# Battery.net
KiCad netlist of a schematic drawn in Altium Designer
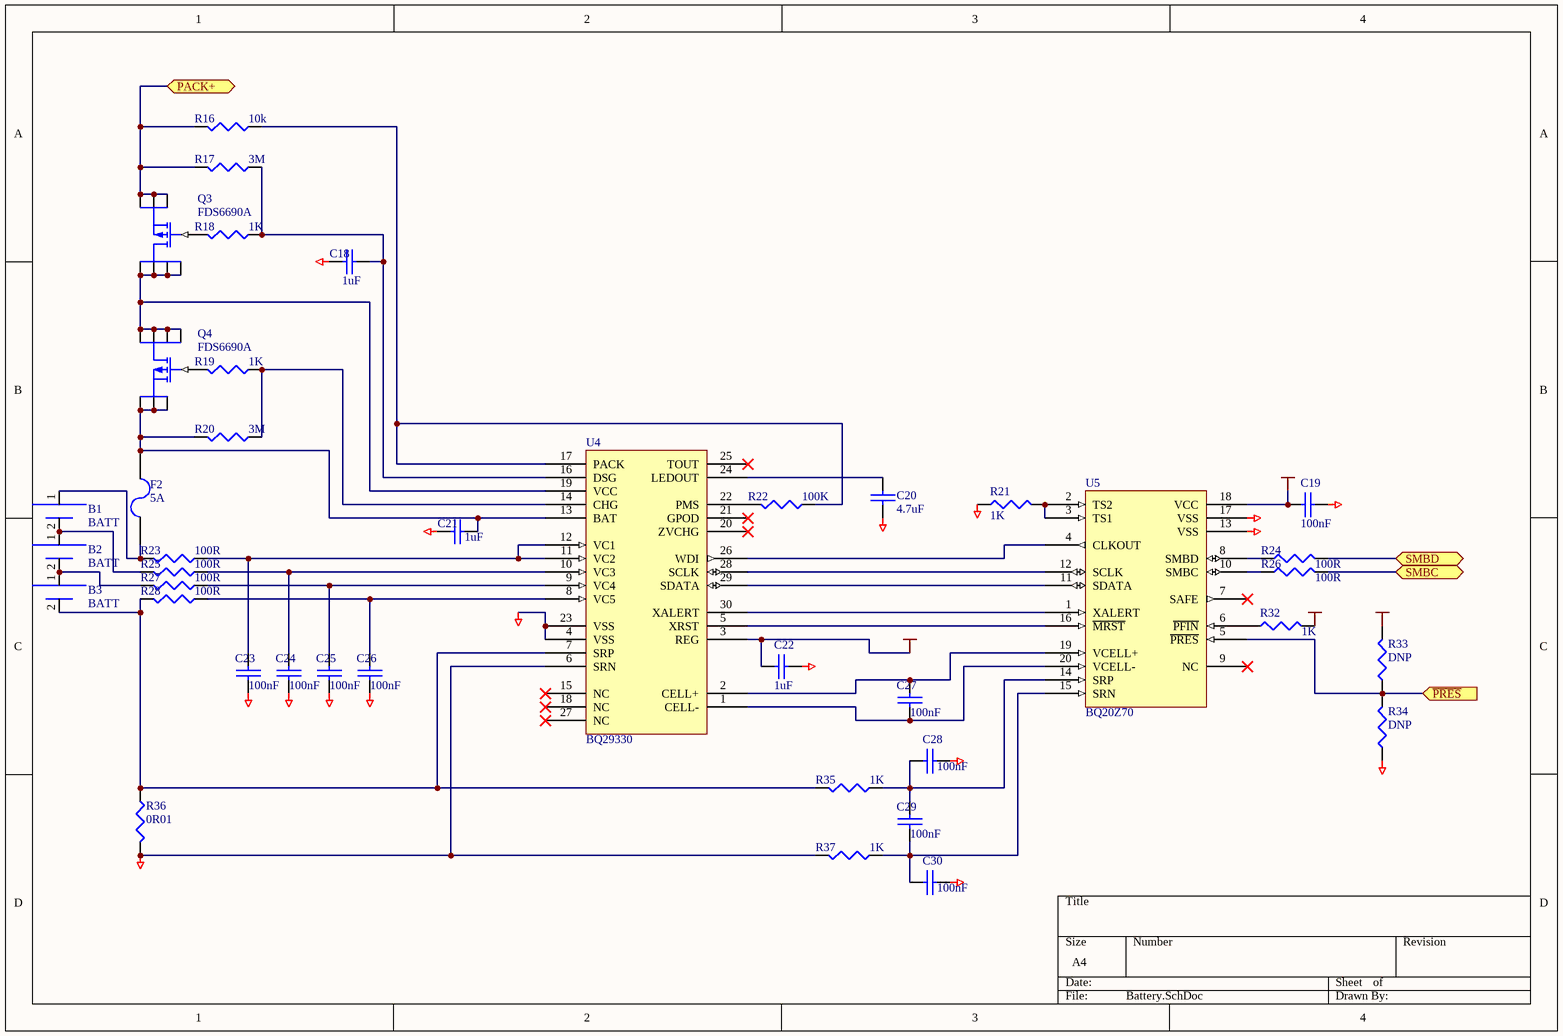
[diagram p0: Battery.SchDoc]

(export (version "E")
  (design (tool "Eeschema 10.0.6"))
  (components
    (comp (ref "B1")
      (value "BATT")
      (footprint "StandardLiIonCell")
      (libsource (lib "Miscellaneous") (part "BATT"))
    )
    (comp (ref "B2")
      (value "BATT")
      (footprint "StandardLiIonCell")
      (libsource (lib "Miscellaneous") (part "BATT"))
    )
    (comp (ref "B3")
      (value "BATT")
      (footprint "StandardLiIonCell")
      (libsource (lib "Miscellaneous") (part "BATT"))
    )
    (comp (ref "C18")
      (value "1uF")
      (footprint "0805")
      (description "Capacitor")
      (libsource (lib "*") (part "CAP"))
    )
    (comp (ref "C19")
      (value "100nF")
      (footprint "0603")
      (description "Capacitor")
      (libsource (lib "*") (part "CAP"))
    )
    (comp (ref "C20")
      (value "4.7uF")
      (footprint "0805")
      (description "Capacitor")
      (libsource (lib "*") (part "CAP"))
    )
    (comp (ref "C21")
      (value "1uF")
      (footprint "0805")
      (description "Capacitor")
      (libsource (lib "*") (part "CAP"))
    )
    (comp (ref "C22")
      (value "1uF")
      (footprint "0805")
      (description "Capacitor")
      (libsource (lib "*") (part "CAP"))
    )
    (comp (ref "C23")
      (value "100nF")
      (footprint "0603")
      (description "Capacitor")
      (libsource (lib "*") (part "CAP"))
    )
    (comp (ref "C24")
      (value "100nF")
      (footprint "0603")
      (description "Capacitor")
      (libsource (lib "*") (part "CAP"))
    )
    (comp (ref "C25")
      (value "100nF")
      (footprint "0603")
      (description "Capacitor")
      (libsource (lib "*") (part "CAP"))
    )
    (comp (ref "C26")
      (value "100nF")
      (footprint "0603")
      (description "Capacitor")
      (libsource (lib "*") (part "CAP"))
    )
    (comp (ref "C27")
      (value "100nF")
      (footprint "0603")
      (description "Capacitor")
      (libsource (lib "*") (part "CAP"))
    )
    (comp (ref "C28")
      (value "100nF")
      (footprint "0603")
      (description "Capacitor")
      (libsource (lib "*") (part "CAP"))
    )
    (comp (ref "C29")
      (value "100nF")
      (footprint "0603")
      (description "Capacitor")
      (libsource (lib "*") (part "CAP"))
    )
    (comp (ref "C30")
      (value "100nF")
      (footprint "0603")
      (description "Capacitor")
      (libsource (lib "*") (part "CAP"))
    )
    (comp (ref "F2")
      (value "5A")
      (footprint "LITTELFUSE-154")
      (description "Fuse")
      (libsource (lib "*") (part "FUSE2"))
    )
    (comp (ref "Q3")
      (value "FDS6690A")
      (footprint "SO8")
      (description "N-type MOSFET")
      (libsource (lib "RCLDQ") (part "FDS6690A"))
    )
    (comp (ref "Q4")
      (value "FDS6690A")
      (footprint "SO8")
      (description "N-type MOSFET")
      (libsource (lib "RCLDQ") (part "FDS6690A"))
    )
    (comp (ref "R16")
      (value "10k")
      (footprint "0603")
      (description "Resistor")
      (libsource (lib "SunswiftLib20030312RR") (part "RES1"))
    )
    (comp (ref "R17")
      (value "3M")
      (footprint "0603")
      (description "Resistor")
      (libsource (lib "SunswiftLib20030312RR") (part "RES1"))
    )
    (comp (ref "R18")
      (value "1K")
      (footprint "0603")
      (description "Resistor")
      (libsource (lib "SunswiftLib20030312RR") (part "RES1"))
    )
    (comp (ref "R19")
      (value "1K")
      (footprint "0603")
      (description "Resistor")
      (libsource (lib "SunswiftLib20030312RR") (part "RES1"))
    )
    (comp (ref "R20")
      (value "3M")
      (footprint "0603")
      (description "Resistor")
      (libsource (lib "SunswiftLib20030312RR") (part "RES1"))
    )
    (comp (ref "R21")
      (value "1K")
      (footprint "0603")
      (description "Resistor")
      (libsource (lib "SunswiftLib20030312RR") (part "RES1"))
    )
    (comp (ref "R22")
      (value "100K")
      (footprint "0603")
      (description "Resistor")
      (libsource (lib "SunswiftLib20030312RR") (part "RES1"))
    )
    (comp (ref "R23")
      (value "100R")
      (footprint "0603")
      (description "Resistor")
      (libsource (lib "SunswiftLib20030312RR") (part "RES1"))
    )
    (comp (ref "R24")
      (value "100R")
      (footprint "0603")
      (description "Resistor")
      (libsource (lib "SunswiftLib20030312RR") (part "RES1"))
    )
    (comp (ref "R25")
      (value "100R")
      (footprint "0603")
      (description "Resistor")
      (libsource (lib "SunswiftLib20030312RR") (part "RES1"))
    )
    (comp (ref "R26")
      (value "100R")
      (footprint "0603")
      (description "Resistor")
      (libsource (lib "SunswiftLib20030312RR") (part "RES1"))
    )
    (comp (ref "R27")
      (value "100R")
      (footprint "0603")
      (description "Resistor")
      (libsource (lib "SunswiftLib20030312RR") (part "RES1"))
    )
    (comp (ref "R28")
      (value "100R")
      (footprint "0603")
      (description "Resistor")
      (libsource (lib "SunswiftLib20030312RR") (part "RES1"))
    )
    (comp (ref "R32")
      (value "1K")
      (footprint "0603")
      (description "Resistor")
      (libsource (lib "SunswiftLib20030312RR") (part "RES1"))
    )
    (comp (ref "R33")
      (value "DNP")
      (footprint "0603")
      (description "Resistor")
      (libsource (lib "SunswiftLib20030312RR") (part "RES1"))
    )
    (comp (ref "R34")
      (value "DNP")
      (footprint "0603")
      (description "Resistor")
      (libsource (lib "SunswiftLib20030312RR") (part "RES1"))
    )
    (comp (ref "R35")
      (value "1K")
      (footprint "0603")
      (description "Resistor")
      (libsource (lib "SunswiftLib20030312RR") (part "RES1"))
    )
    (comp (ref "R36")
      (value "0R01")
      (footprint "2010")
      (description "Resistor")
      (libsource (lib "RCLDQ") (part "RES1"))
    )
    (comp (ref "R37")
      (value "1K")
      (footprint "0603")
      (description "Resistor")
      (libsource (lib "SunswiftLib20030312RR") (part "RES1"))
    )
    (comp (ref "U4")
      (value "BQ29330")
      (footprint "TSSOP30")
      (libsource (lib "MiscellaneousIC") (part "BQ29330"))
    )
    (comp (ref "U5")
      (value "BQ20Z70")
      (footprint "TSSOP20")
      (libsource (lib "MiscellaneousIC") (part "BQ20Z70"))
    )
  )
  (nets
    (net (code "1") (name "/PACK+") (class "Default")
      (node (ref "Q3") (pin "1") (pinfunction "S_1") (pintype "bidirectional"))
      (node (ref "Q3") (pin "2") (pinfunction "S_2") (pintype "bidirectional"))
      (node (ref "Q3") (pin "3") (pinfunction "S_3") (pintype "bidirectional"))
      (node (ref "R16") (pin "2") (pinfunction "2_2") (pintype "passive"))
      (node (ref "R17") (pin "2") (pinfunction "2_2") (pintype "passive"))
    )
    (net (code "2") (name "/SMBC") (class "Default")
      (node (ref "R26") (pin "2") (pinfunction "2_2") (pintype "passive"))
    )
    (net (code "3") (name "/SMBD") (class "Default")
      (node (ref "R24") (pin "2") (pinfunction "2_2") (pintype "passive"))
    )
    (net (code "4") (name "/~{PRES}") (class "Default")
      (node (ref "R33") (pin "1") (pinfunction "1_1") (pintype "passive"))
      (node (ref "R34") (pin "2") (pinfunction "2_2") (pintype "passive"))
      (node (ref "U5") (pin "5") (pinfunction "~{PRES}_5") (pintype "input"))
    )
    (net (code "5") (name "BATT_VCC") (class "Default")
      (node (ref "C19") (pin "1") (pinfunction "1_1") (pintype "passive"))
      (node (ref "C22") (pin "1") (pinfunction "1_1") (pintype "passive"))
      (node (ref "R32") (pin "2") (pinfunction "2_2") (pintype "passive"))
      (node (ref "R33") (pin "2") (pinfunction "2_2") (pintype "passive"))
      (node (ref "U4") (pin "3") (pinfunction "REG_3") (pintype "passive"))
      (node (ref "U5") (pin "18") (pinfunction "VCC_18") (pintype "power_in"))
    )
    (net (code "6") (name "GND") (class "Default")
      (node (ref "C18") (pin "2") (pinfunction "2_2") (pintype "passive"))
      (node (ref "C19") (pin "2") (pinfunction "2_2") (pintype "passive"))
      (node (ref "C20") (pin "2") (pinfunction "2_2") (pintype "passive"))
      (node (ref "C21") (pin "2") (pinfunction "2_2") (pintype "passive"))
      (node (ref "C22") (pin "2") (pinfunction "2_2") (pintype "passive"))
      (node (ref "C23") (pin "2") (pinfunction "2_2") (pintype "passive"))
      (node (ref "C24") (pin "2") (pinfunction "2_2") (pintype "passive"))
      (node (ref "C25") (pin "2") (pinfunction "2_2") (pintype "passive"))
      (node (ref "C26") (pin "2") (pinfunction "2_2") (pintype "passive"))
      (node (ref "C28") (pin "2") (pinfunction "2_2") (pintype "passive"))
      (node (ref "C30") (pin "2") (pinfunction "2_2") (pintype "passive"))
      (node (ref "R21") (pin "1") (pinfunction "1_1") (pintype "passive"))
      (node (ref "R34") (pin "1") (pinfunction "1_1") (pintype "passive"))
      (node (ref "R36") (pin "2") (pinfunction "2_2") (pintype "passive"))
      (node (ref "R37") (pin "2") (pinfunction "2_2") (pintype "passive"))
      (node (ref "U4") (pin "23") (pinfunction "VSS_23") (pintype "power_in"))
      (node (ref "U4") (pin "4") (pinfunction "VSS_4") (pintype "power_in"))
      (node (ref "U4") (pin "6") (pinfunction "SRN_6") (pintype "passive"))
      (node (ref "U5") (pin "13") (pinfunction "VSS_13") (pintype "power_in"))
      (node (ref "U5") (pin "17") (pinfunction "VSS_17") (pintype "power_in"))
    )
    (net (code "7") (name "Net-(B1-+)") (class "Default")
      (node (ref "B1") (pin "1") (pinfunction "+_1") (pintype "power_in"))
      (node (ref "F2") (pin "1") (pinfunction "1_1") (pintype "passive"))
      (node (ref "R23") (pin "2") (pinfunction "2_2") (pintype "passive"))
    )
    (net (code "8") (name "Net-(B1--)") (class "Default")
      (node (ref "B1") (pin "2") (pinfunction "-_2") (pintype "power_in"))
      (node (ref "B2") (pin "1") (pinfunction "+_1") (pintype "power_in"))
      (node (ref "R25") (pin "2") (pinfunction "2_2") (pintype "passive"))
    )
    (net (code "9") (name "Net-(B2--)") (class "Default")
      (node (ref "B2") (pin "2") (pinfunction "-_2") (pintype "power_in"))
      (node (ref "B3") (pin "1") (pinfunction "+_1") (pintype "power_in"))
      (node (ref "R27") (pin "2") (pinfunction "2_2") (pintype "passive"))
    )
    (net (code "10") (name "Net-(B3--)") (class "Default")
      (node (ref "B3") (pin "2") (pinfunction "-_2") (pintype "power_in"))
      (node (ref "R28") (pin "2") (pinfunction "2_2") (pintype "passive"))
      (node (ref "R35") (pin "2") (pinfunction "2_2") (pintype "passive"))
      (node (ref "R36") (pin "1") (pinfunction "1_1") (pintype "passive"))
      (node (ref "U4") (pin "7") (pinfunction "SRP_7") (pintype "passive"))
    )
    (net (code "11") (name "Net-(Q3-G)") (class "Default")
      (node (ref "Q3") (pin "4") (pinfunction "G_4") (pintype "input"))
      (node (ref "R18") (pin "2") (pinfunction "2_2") (pintype "passive"))
    )
    (net (code "12") (name "Net-(Q4-G)") (class "Default")
      (node (ref "Q4") (pin "4") (pinfunction "G_4") (pintype "input"))
      (node (ref "R19") (pin "2") (pinfunction "2_2") (pintype "passive"))
    )
    (net (code "13") (name "Net-(U4-BAT)") (class "Default")
      (node (ref "C21") (pin "1") (pinfunction "1_1") (pintype "passive"))
      (node (ref "F2") (pin "2") (pinfunction "2_2") (pintype "passive"))
      (node (ref "Q4") (pin "1") (pinfunction "S_1") (pintype "bidirectional"))
      (node (ref "Q4") (pin "2") (pinfunction "S_2") (pintype "bidirectional"))
      (node (ref "Q4") (pin "3") (pinfunction "S_3") (pintype "bidirectional"))
      (node (ref "R20") (pin "2") (pinfunction "2_2") (pintype "passive"))
      (node (ref "U4") (pin "13") (pinfunction "BAT_13") (pintype "power_in"))
    )
    (net (code "14") (name "Net-(U4-CELL+)") (class "Default")
      (node (ref "C27") (pin "1") (pinfunction "1_1") (pintype "passive"))
      (node (ref "U4") (pin "2") (pinfunction "CELL+_2") (pintype "passive"))
      (node (ref "U5") (pin "19") (pinfunction "VCELL+_19") (pintype "input"))
    )
    (net (code "15") (name "Net-(U4-CELL-)") (class "Default")
      (node (ref "C27") (pin "2") (pinfunction "2_2") (pintype "passive"))
      (node (ref "U4") (pin "1") (pinfunction "CELL-_1") (pintype "power_in"))
      (node (ref "U5") (pin "20") (pinfunction "VCELL-_20") (pintype "input"))
    )
    (net (code "16") (name "Net-(U4-CHG)") (class "Default")
      (node (ref "R19") (pin "1") (pinfunction "1_1") (pintype "passive"))
      (node (ref "R20") (pin "1") (pinfunction "1_1") (pintype "passive"))
      (node (ref "U4") (pin "14") (pinfunction "CHG_14") (pintype "power_in"))
    )
    (net (code "17") (name "Net-(U4-DSG)") (class "Default")
      (node (ref "C18") (pin "1") (pinfunction "1_1") (pintype "passive"))
      (node (ref "R17") (pin "1") (pinfunction "1_1") (pintype "passive"))
      (node (ref "R18") (pin "1") (pinfunction "1_1") (pintype "passive"))
      (node (ref "U4") (pin "16") (pinfunction "DSG_16") (pintype "passive"))
    )
    (net (code "18") (name "Net-(U4-LEDOUT)") (class "Default")
      (node (ref "C20") (pin "1") (pinfunction "1_1") (pintype "passive"))
      (node (ref "U4") (pin "24") (pinfunction "LEDOUT_24") (pintype "passive"))
    )
    (net (code "19") (name "Net-(U4-PACK)") (class "Default")
      (node (ref "R16") (pin "1") (pinfunction "1_1") (pintype "passive"))
      (node (ref "R22") (pin "1") (pinfunction "1_1") (pintype "passive"))
      (node (ref "U4") (pin "17") (pinfunction "PACK_17") (pintype "passive"))
    )
    (net (code "20") (name "Net-(U4-PMS)") (class "Default")
      (node (ref "R22") (pin "2") (pinfunction "2_2") (pintype "passive"))
      (node (ref "U4") (pin "22") (pinfunction "PMS_22") (pintype "passive"))
    )
    (net (code "21") (name "Net-(U4-SCLK)") (class "Default")
      (node (ref "U4") (pin "28") (pinfunction "SCLK_28") (pintype "bidirectional"))
      (node (ref "U5") (pin "12") (pinfunction "SCLK_12") (pintype "bidirectional"))
    )
    (net (code "22") (name "Net-(U4-SDATA)") (class "Default")
      (node (ref "U4") (pin "29") (pinfunction "SDATA_29") (pintype "bidirectional"))
      (node (ref "U5") (pin "11") (pinfunction "SDATA_11") (pintype "bidirectional"))
    )
    (net (code "23") (name "Net-(U4-VC1)") (class "Default")
      (node (ref "C23") (pin "1") (pinfunction "1_1") (pintype "passive"))
      (node (ref "R23") (pin "1") (pinfunction "1_1") (pintype "passive"))
      (node (ref "U4") (pin "11") (pinfunction "VC2_11") (pintype "input"))
      (node (ref "U4") (pin "12") (pinfunction "VC1_12") (pintype "input"))
    )
    (net (code "24") (name "Net-(U4-VC3)") (class "Default")
      (node (ref "C24") (pin "1") (pinfunction "1_1") (pintype "passive"))
      (node (ref "R25") (pin "1") (pinfunction "1_1") (pintype "passive"))
      (node (ref "U4") (pin "10") (pinfunction "VC3_10") (pintype "input"))
    )
    (net (code "25") (name "Net-(U4-VC4)") (class "Default")
      (node (ref "C25") (pin "1") (pinfunction "1_1") (pintype "passive"))
      (node (ref "R27") (pin "1") (pinfunction "1_1") (pintype "passive"))
      (node (ref "U4") (pin "9") (pinfunction "VC4_9") (pintype "input"))
    )
    (net (code "26") (name "Net-(U4-VC5)") (class "Default")
      (node (ref "C26") (pin "1") (pinfunction "1_1") (pintype "passive"))
      (node (ref "R28") (pin "1") (pinfunction "1_1") (pintype "passive"))
      (node (ref "U4") (pin "8") (pinfunction "VC5_8") (pintype "input"))
    )
    (net (code "27") (name "Net-(U4-VCC)") (class "Default")
      (node (ref "Q3") (pin "5") (pinfunction "D_5") (pintype "bidirectional"))
      (node (ref "Q3") (pin "6") (pinfunction "D_6") (pintype "bidirectional"))
      (node (ref "Q3") (pin "7") (pinfunction "D_7") (pintype "bidirectional"))
      (node (ref "Q3") (pin "8") (pinfunction "D_8") (pintype "bidirectional"))
      (node (ref "Q4") (pin "5") (pinfunction "D_5") (pintype "bidirectional"))
      (node (ref "Q4") (pin "6") (pinfunction "D_6") (pintype "bidirectional"))
      (node (ref "Q4") (pin "7") (pinfunction "D_7") (pintype "bidirectional"))
      (node (ref "Q4") (pin "8") (pinfunction "D_8") (pintype "bidirectional"))
      (node (ref "U4") (pin "19") (pinfunction "VCC_19") (pintype "power_in"))
    )
    (net (code "28") (name "Net-(U4-WDI)") (class "Default")
      (node (ref "U4") (pin "26") (pinfunction "WDI_26") (pintype "output"))
      (node (ref "U5") (pin "4") (pinfunction "CLKOUT_4") (pintype "output"))
    )
    (net (code "29") (name "Net-(U4-XALERT)") (class "Default")
      (node (ref "U4") (pin "30") (pinfunction "XALERT_30") (pintype "passive"))
      (node (ref "U5") (pin "1") (pinfunction "XALERT_1") (pintype "input"))
    )
    (net (code "30") (name "Net-(U4-XRST)") (class "Default")
      (node (ref "U4") (pin "5") (pinfunction "XRST_5") (pintype "passive"))
      (node (ref "U5") (pin "16") (pinfunction "~{MRST}_16") (pintype "input"))
    )
    (net (code "31") (name "Net-(U5-SMBC)") (class "Default")
      (node (ref "R26") (pin "1") (pinfunction "1_1") (pintype "passive"))
      (node (ref "U5") (pin "10") (pinfunction "SMBC_10") (pintype "bidirectional"))
    )
    (net (code "32") (name "Net-(U5-SMBD)") (class "Default")
      (node (ref "R24") (pin "1") (pinfunction "1_1") (pintype "passive"))
      (node (ref "U5") (pin "8") (pinfunction "SMBD_8") (pintype "bidirectional"))
    )
    (net (code "33") (name "Net-(U5-SRN)") (class "Default")
      (node (ref "C29") (pin "2") (pinfunction "2_2") (pintype "passive"))
      (node (ref "C30") (pin "1") (pinfunction "1_1") (pintype "passive"))
      (node (ref "R37") (pin "1") (pinfunction "1_1") (pintype "passive"))
      (node (ref "U5") (pin "15") (pinfunction "SRN_15") (pintype "input"))
    )
    (net (code "34") (name "Net-(U5-SRP)") (class "Default")
      (node (ref "C28") (pin "1") (pinfunction "1_1") (pintype "passive"))
      (node (ref "C29") (pin "1") (pinfunction "1_1") (pintype "passive"))
      (node (ref "R35") (pin "1") (pinfunction "1_1") (pintype "passive"))
      (node (ref "U5") (pin "14") (pinfunction "SRP_14") (pintype "input"))
    )
    (net (code "35") (name "Net-(U5-TS1)") (class "Default")
      (node (ref "R21") (pin "2") (pinfunction "2_2") (pintype "passive"))
      (node (ref "U5") (pin "2") (pinfunction "TS2_2") (pintype "input"))
      (node (ref "U5") (pin "3") (pinfunction "TS1_3") (pintype "input"))
    )
    (net (code "36") (name "Net-(U5-~{PFIN})") (class "Default")
      (node (ref "R32") (pin "1") (pinfunction "1_1") (pintype "passive"))
      (node (ref "U5") (pin "6") (pinfunction "~{PFIN}_6") (pintype "input"))
    )
    (net (code "37") (name "unconnected-(U4-GPOD-Pad21)") (class "Default")
      (node (ref "U4") (pin "21") (pinfunction "GPOD_21") (pintype "passive+no_connect"))
    )
    (net (code "38") (name "unconnected-(U4-NC-Pad15)") (class "Default")
      (node (ref "U4") (pin "15") (pinfunction "NC_15") (pintype "passive+no_connect"))
    )
    (net (code "39") (name "unconnected-(U4-NC-Pad18)") (class "Default")
      (node (ref "U4") (pin "18") (pinfunction "NC_18") (pintype "passive+no_connect"))
    )
    (net (code "40") (name "unconnected-(U4-NC-Pad27)") (class "Default")
      (node (ref "U4") (pin "27") (pinfunction "NC_27") (pintype "passive+no_connect"))
    )
    (net (code "41") (name "unconnected-(U4-TOUT-Pad25)") (class "Default")
      (node (ref "U4") (pin "25") (pinfunction "TOUT_25") (pintype "passive+no_connect"))
    )
    (net (code "42") (name "unconnected-(U4-ZVCHG-Pad20)") (class "Default")
      (node (ref "U4") (pin "20") (pinfunction "ZVCHG_20") (pintype "passive+no_connect"))
    )
    (net (code "43") (name "unconnected-(U5-NC-Pad9)") (class "Default")
      (node (ref "U5") (pin "9") (pinfunction "NC_9") (pintype "passive+no_connect"))
    )
    (net (code "44") (name "unconnected-(U5-SAFE-Pad7)") (class "Default")
      (node (ref "U5") (pin "7") (pinfunction "SAFE_7") (pintype "output+no_connect"))
    )
  )
)
